# ADS1298.net
KiCad netlist of a schematic drawn in Altium Designer
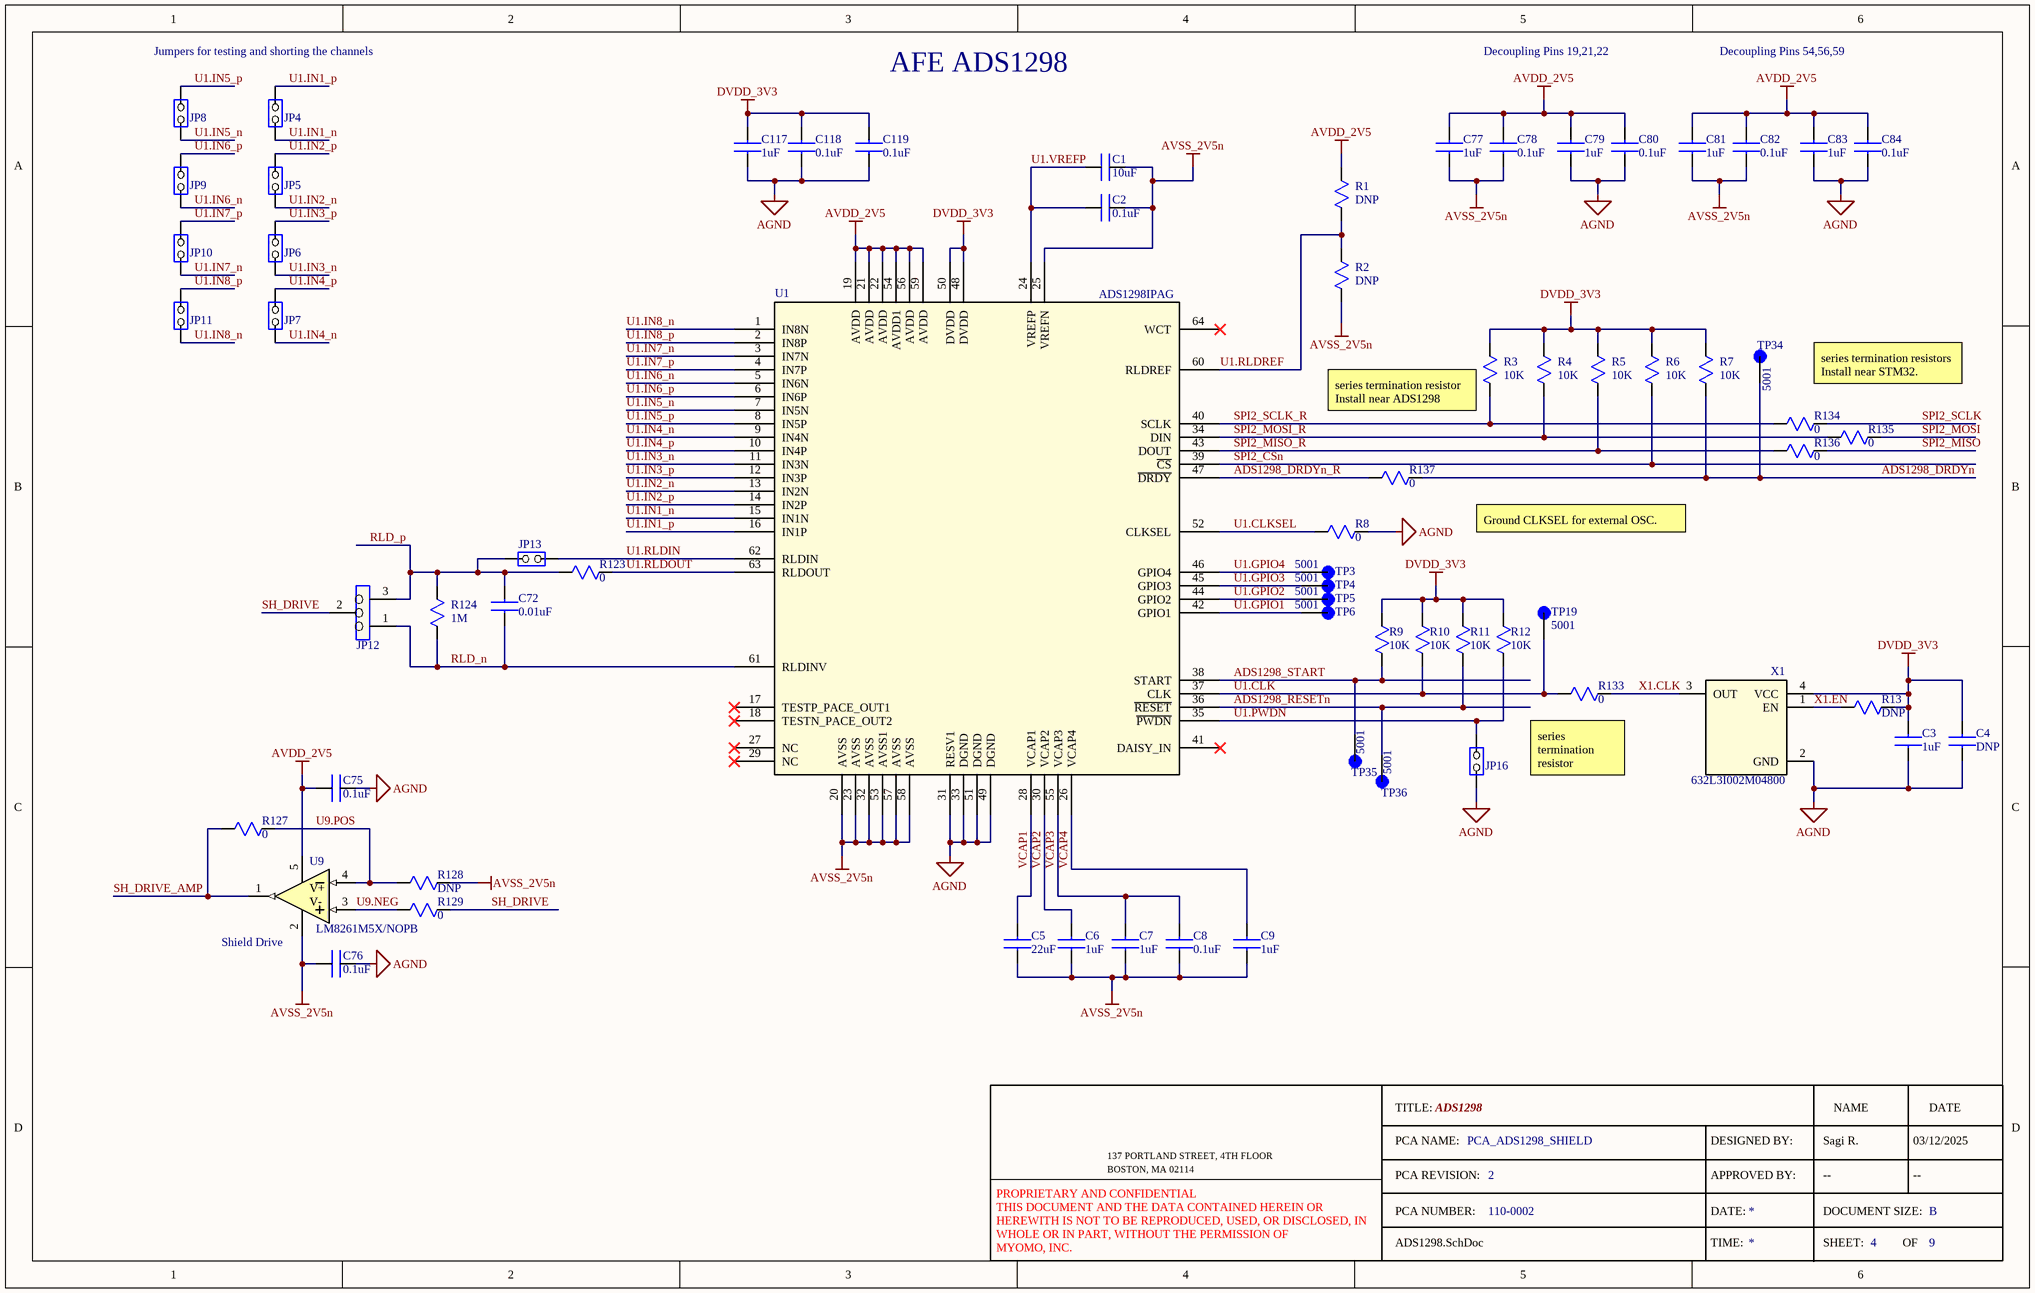
[diagram p0: ADS1298.SchDoc]

(export (version "E")
  (design (tool "Eeschema 10.0.6"))
  (components
    (comp (ref "C1")
      (value "10uF")
      (footprint "1210")
      (description "CAP CER 10UF 25V X7R 1210")
      (fields (field (name "MFG") "SUMSUNG"))
      (libsource (lib "Myomo_SCH_Library") (part "C_1210_CER_10uF_25V_X7R"))
    )
    (comp (ref "C2")
      (value "0.1uF")
      (footprint "0402")
      (description "CAP CER 0.1UF 50V X7R 0402")
      (fields (field (name "MFG") "Samsung"))
      (libsource (lib "") (part "C_0402_CER_0.1uF_50V_X7R_1"))
    )
    (comp (ref "C3")
      (value "1uF")
      (footprint "0603")
      (description "CAP CER 1UF 50V X7R 0603")
      (fields (field (name "MFG") "YAGEO"))
      (libsource (lib "Myomo_SCH_Library") (part "C_0603_CER_1uF_50V_X7R"))
    )
    (comp (ref "C4")
      (value "DNP")
      (footprint "0603")
      (description "CAP CER 0603 DNP")
      (libsource (lib "Myomo_SCH_Library") (part "C_0603_DNP"))
    )
    (comp (ref "C5")
      (value "22uF")
      (footprint "1210")
      (description "CAP CER 22UF 25V X7R 1210")
      (fields (field (name "MFG") "SUMSUNG"))
      (libsource (lib "Myomo_SCH_Library") (part "C_1210_CER_22uF_25V_X7R"))
    )
    (comp (ref "C6")
      (value "1uF")
      (footprint "0603")
      (description "CAP CER 1UF 50V X7R 0603")
      (fields (field (name "MFG") "YAGEO"))
      (libsource (lib "Myomo_SCH_Library") (part "C_0603_CER_1uF_50V_X7R"))
    )
    (comp (ref "C7")
      (value "1uF")
      (footprint "0603")
      (description "CAP CER 1UF 50V X7R 0603")
      (fields (field (name "MFG") "YAGEO"))
      (libsource (lib "Myomo_SCH_Library") (part "C_0603_CER_1uF_50V_X7R"))
    )
    (comp (ref "C8")
      (value "0.1uF")
      (footprint "0402")
      (description "CAP CER 0.1UF 50V X7R 0402")
      (fields (field (name "MFG") "Samsung"))
      (libsource (lib "Myomo_SCH_Library") (part "C_0402_CER_0.1uF_50V_X7R"))
    )
    (comp (ref "C9")
      (value "1uF")
      (footprint "0603")
      (description "CAP CER 1UF 50V X7R 0603")
      (fields (field (name "MFG") "YAGEO"))
      (libsource (lib "Myomo_SCH_Library") (part "C_0603_CER_1uF_50V_X7R"))
    )
    (comp (ref "C72")
      (value "0.01uF")
      (footprint "0603")
      (description "CAP CER 10000PF 100V X7R 0603")
      (fields (field (name "MFG") "SAMSUNG"))
      (libsource (lib "Myomo_SCH_Library") (part "C_0603_CER_0.01uF_100V_X7R"))
    )
    (comp (ref "C75")
      (value "0.1uF")
      (footprint "0402")
      (description "CAP CER 0.1UF 50V X7R 0402")
      (fields (field (name "MFG") "Samsung"))
      (libsource (lib "") (part "C_0402_CER_0.1uF_50V_X7R_1"))
    )
    (comp (ref "C76")
      (value "0.1uF")
      (footprint "0402")
      (description "CAP CER 0.1UF 50V X7R 0402")
      (fields (field (name "MFG") "Samsung"))
      (libsource (lib "") (part "C_0402_CER_0.1uF_50V_X7R_1"))
    )
    (comp (ref "C77")
      (value "1uF")
      (footprint "0603")
      (description "CAP CER 1UF 50V X7R 0603")
      (fields (field (name "MFG") "YAGEO"))
      (libsource (lib "Myomo_SCH_Library") (part "C_0603_CER_1uF_50V_X7R"))
    )
    (comp (ref "C78")
      (value "0.1uF")
      (footprint "0402")
      (description "CAP CER 0.1UF 50V X7R 0402")
      (fields (field (name "MFG") "Samsung"))
      (libsource (lib "Myomo_SCH_Library") (part "C_0402_CER_0.1uF_50V_X7R"))
    )
    (comp (ref "C79")
      (value "1uF")
      (footprint "0603")
      (description "CAP CER 1UF 50V X7R 0603")
      (fields (field (name "MFG") "YAGEO"))
      (libsource (lib "Myomo_SCH_Library") (part "C_0603_CER_1uF_50V_X7R"))
    )
    (comp (ref "C80")
      (value "0.1uF")
      (footprint "0402")
      (description "CAP CER 0.1UF 50V X7R 0402")
      (fields (field (name "MFG") "Samsung"))
      (libsource (lib "Myomo_SCH_Library") (part "C_0402_CER_0.1uF_50V_X7R"))
    )
    (comp (ref "C81")
      (value "1uF")
      (footprint "0603")
      (description "CAP CER 1UF 50V X7R 0603")
      (fields (field (name "MFG") "YAGEO"))
      (libsource (lib "Myomo_SCH_Library") (part "C_0603_CER_1uF_50V_X7R"))
    )
    (comp (ref "C82")
      (value "0.1uF")
      (footprint "0402")
      (description "CAP CER 0.1UF 50V X7R 0402")
      (fields (field (name "MFG") "Samsung"))
      (libsource (lib "Myomo_SCH_Library") (part "C_0402_CER_0.1uF_50V_X7R"))
    )
    (comp (ref "C83")
      (value "1uF")
      (footprint "0603")
      (description "CAP CER 1UF 50V X7R 0603")
      (fields (field (name "MFG") "YAGEO"))
      (libsource (lib "Myomo_SCH_Library") (part "C_0603_CER_1uF_50V_X7R"))
    )
    (comp (ref "C84")
      (value "0.1uF")
      (footprint "0402")
      (description "CAP CER 0.1UF 50V X7R 0402")
      (fields (field (name "MFG") "Samsung"))
      (libsource (lib "Myomo_SCH_Library") (part "C_0402_CER_0.1uF_50V_X7R"))
    )
    (comp (ref "C117")
      (value "1uF")
      (footprint "0603")
      (description "CAP CER 1UF 50V X7R 0603")
      (fields (field (name "MFG") "YAGEO"))
      (libsource (lib "Myomo_SCH_Library") (part "C_0603_CER_1uF_50V_X7R"))
    )
    (comp (ref "C118")
      (value "0.1uF")
      (footprint "0402")
      (description "CAP CER 0.1UF 50V X7R 0402")
      (fields (field (name "MFG") "Samsung"))
      (libsource (lib "Myomo_SCH_Library") (part "C_0402_CER_0.1uF_50V_X7R"))
    )
    (comp (ref "C119")
      (value "0.1uF")
      (footprint "0402")
      (description "CAP CER 0.1UF 50V X7R 0402")
      (fields (field (name "MFG") "Samsung"))
      (libsource (lib "Myomo_SCH_Library") (part "C_0402_CER_0.1uF_50V_X7R"))
    )
    (comp (ref "JP4")
      (value "JP_1x2_TSW-102-07-F-S")
      (footprint "JP_1x2_TSW-102-07-F-S")
      (description "CONN HEADER VERT 2POS 2.54MM")
      (fields (field (name "MFG") "SAMTEC"))
      (libsource (lib "Myomo_SCH_Library") (part "JP_1x2_TSW-102-07-F-S"))
    )
    (comp (ref "JP5")
      (value "JP_1x2_TSW-102-07-F-S")
      (footprint "JP_1x2_TSW-102-07-F-S")
      (description "CONN HEADER VERT 2POS 2.54MM")
      (fields (field (name "MFG") "SAMTEC"))
      (libsource (lib "Myomo_SCH_Library") (part "JP_1x2_TSW-102-07-F-S"))
    )
    (comp (ref "JP6")
      (value "JP_1x2_TSW-102-07-F-S")
      (footprint "JP_1x2_TSW-102-07-F-S")
      (description "CONN HEADER VERT 2POS 2.54MM")
      (fields (field (name "MFG") "SAMTEC"))
      (libsource (lib "Myomo_SCH_Library") (part "JP_1x2_TSW-102-07-F-S"))
    )
    (comp (ref "JP7")
      (value "JP_1x2_TSW-102-07-F-S")
      (footprint "JP_1x2_TSW-102-07-F-S")
      (description "CONN HEADER VERT 2POS 2.54MM")
      (fields (field (name "MFG") "SAMTEC"))
      (libsource (lib "Myomo_SCH_Library") (part "JP_1x2_TSW-102-07-F-S"))
    )
    (comp (ref "JP8")
      (value "JP_1x2_TSW-102-07-F-S")
      (footprint "JP_1x2_TSW-102-07-F-S")
      (description "CONN HEADER VERT 2POS 2.54MM")
      (fields (field (name "MFG") "SAMTEC"))
      (libsource (lib "Myomo_SCH_Library") (part "JP_1x2_TSW-102-07-F-S"))
    )
    (comp (ref "JP9")
      (value "JP_1x2_TSW-102-07-F-S")
      (footprint "JP_1x2_TSW-102-07-F-S")
      (description "CONN HEADER VERT 2POS 2.54MM")
      (fields (field (name "MFG") "SAMTEC"))
      (libsource (lib "Myomo_SCH_Library") (part "JP_1x2_TSW-102-07-F-S"))
    )
    (comp (ref "JP10")
      (value "JP_1x2_TSW-102-07-F-S")
      (footprint "JP_1x2_TSW-102-07-F-S")
      (description "CONN HEADER VERT 2POS 2.54MM")
      (fields (field (name "MFG") "SAMTEC"))
      (libsource (lib "Myomo_SCH_Library") (part "JP_1x2_TSW-102-07-F-S"))
    )
    (comp (ref "JP11")
      (value "JP_1x2_TSW-102-07-F-S")
      (footprint "JP_1x2_TSW-102-07-F-S")
      (description "CONN HEADER VERT 2POS 2.54MM")
      (fields (field (name "MFG") "SAMTEC"))
      (libsource (lib "Myomo_SCH_Library") (part "JP_1x2_TSW-102-07-F-S"))
    )
    (comp (ref "JP12")
      (value "JP_1x3_TSW-103-07-F-S")
      (footprint "JP_1x3_TSW-103-07-F-S")
      (description "CONN HEADER VERT 2POS 2.54MM")
      (fields (field (name "MFG") "SAMTEC"))
      (libsource (lib "Myomo_SCH_Library") (part "JP_1x3_TSW-103-07-F-S"))
    )
    (comp (ref "JP13")
      (value "JP_1x2_TSW-102-07-F-S")
      (footprint "JP_1x2_TSW-102-07-F-S")
      (description "CONN HEADER VERT 2POS 2.54MM")
      (fields (field (name "MFG") "SAMTEC"))
      (libsource (lib "Myomo_SCH_Library") (part "JP_1x2_TSW-102-07-F-S"))
    )
    (comp (ref "JP16")
      (value "JP_1x2_TSW-102-07-F-S")
      (footprint "JP_1x2_TSW-102-07-F-S")
      (description "CONN HEADER VERT 2POS 2.54MM")
      (fields (field (name "MFG") "SAMTEC"))
      (libsource (lib "Myomo_SCH_Library") (part "JP_1x2_TSW-102-07-F-S"))
    )
    (comp (ref "R1")
      (value "DNP")
      (footprint "0402")
      (description "RES 0402 DNP")
      (libsource (lib "Myomo_SCH_Library") (part "R_0402_DNP"))
    )
    (comp (ref "R2")
      (value "DNP")
      (footprint "0402")
      (description "RES 0402 DNP")
      (libsource (lib "Myomo_SCH_Library") (part "R_0402_DNP"))
    )
    (comp (ref "R3")
      (value "10K")
      (footprint "0402")
      (description "RES SMD 10K OHM 1% 1/10W 0402")
      (fields (field (name "MFG") "Panasonic"))
      (libsource (lib "Myomo_SCH_Library") (part "R_0402_10K_1%_1/10W"))
    )
    (comp (ref "R4")
      (value "10K")
      (footprint "0402")
      (description "RES SMD 10K OHM 1% 1/10W 0402")
      (fields (field (name "MFG") "Panasonic"))
      (libsource (lib "Myomo_SCH_Library") (part "R_0402_10K_1%_1/10W"))
    )
    (comp (ref "R5")
      (value "10K")
      (footprint "0402")
      (description "RES SMD 10K OHM 1% 1/10W 0402")
      (fields (field (name "MFG") "Panasonic"))
      (libsource (lib "Myomo_SCH_Library") (part "R_0402_10K_1%_1/10W"))
    )
    (comp (ref "R6")
      (value "10K")
      (footprint "0402")
      (description "RES SMD 10K OHM 1% 1/10W 0402")
      (fields (field (name "MFG") "Panasonic"))
      (libsource (lib "Myomo_SCH_Library") (part "R_0402_10K_1%_1/10W"))
    )
    (comp (ref "R7")
      (value "10K")
      (footprint "0402")
      (description "RES SMD 10K OHM 1% 1/10W 0402")
      (fields (field (name "MFG") "Panasonic"))
      (libsource (lib "Myomo_SCH_Library") (part "R_0402_10K_1%_1/10W"))
    )
    (comp (ref "R8")
      (value "0")
      (footprint "0603")
      (description "RES 0 OHM JUMPER 1/10W 0603")
      (fields (field (name "MFG") "YAGEO"))
      (libsource (lib "Myomo_SCH_Library") (part "R_0603_0"))
    )
    (comp (ref "R9")
      (value "10K")
      (footprint "0402")
      (description "RES SMD 10K OHM 1% 1/10W 0402")
      (fields (field (name "MFG") "Panasonic"))
      (libsource (lib "Myomo_SCH_Library") (part "R_0402_10K_1%_1/10W"))
    )
    (comp (ref "R10")
      (value "10K")
      (footprint "0402")
      (description "RES SMD 10K OHM 1% 1/10W 0402")
      (fields (field (name "MFG") "Panasonic"))
      (libsource (lib "Myomo_SCH_Library") (part "R_0402_10K_1%_1/10W"))
    )
    (comp (ref "R11")
      (value "10K")
      (footprint "0402")
      (description "RES SMD 10K OHM 1% 1/10W 0402")
      (fields (field (name "MFG") "Panasonic"))
      (libsource (lib "Myomo_SCH_Library") (part "R_0402_10K_1%_1/10W"))
    )
    (comp (ref "R12")
      (value "10K")
      (footprint "0402")
      (description "RES SMD 10K OHM 1% 1/10W 0402")
      (fields (field (name "MFG") "Panasonic"))
      (libsource (lib "Myomo_SCH_Library") (part "R_0402_10K_1%_1/10W"))
    )
    (comp (ref "R13")
      (value "DNP")
      (footprint "0603")
      (description "RES 0603 DNP")
      (libsource (lib "Myomo_SCH_Library") (part "R_0603_DNP"))
    )
    (comp (ref "R123")
      (value "0")
      (footprint "0603")
      (description "RES 0 OHM JUMPER 1/10W 0603")
      (fields (field (name "MFG") "YAGEO"))
      (libsource (lib "Myomo_SCH_Library") (part "R_0603_0"))
    )
    (comp (ref "R124")
      (value "1M")
      (footprint "0402")
      (description "RES SMD 1M OHM 1% 1/10W 0402")
      (fields (field (name "MFG") "Panasonic"))
      (libsource (lib "Myomo_SCH_Library") (part "R_0402_1M_1%_1/10W"))
    )
    (comp (ref "R127")
      (value "0")
      (footprint "0402")
      (description "RES 0 OHM JUMPER 1/10W 0402")
      (fields (field (name "MFG") "YAGEO"))
      (libsource (lib "Myomo_SCH_Library") (part "R_0402_0"))
    )
    (comp (ref "R128")
      (value "DNP")
      (footprint "0402")
      (description "RES 0402 DNP")
      (libsource (lib "") (part "R_0402_DNP_1"))
    )
    (comp (ref "R129")
      (value "0")
      (footprint "0402")
      (description "RES 0 OHM JUMPER 1/10W 0402")
      (fields (field (name "MFG") "YAGEO"))
      (libsource (lib "Myomo_SCH_Library") (part "R_0402_0"))
    )
    (comp (ref "R133")
      (value "0")
      (footprint "0603")
      (description "RES 0 OHM JUMPER 1/10W 0603")
      (fields (field (name "MFG") "YAGEO"))
      (libsource (lib "Myomo_SCH_Library") (part "R_0603_0"))
    )
    (comp (ref "R134")
      (value "0")
      (footprint "0402")
      (description "RES 0 OHM JUMPER 1/10W 0402")
      (fields (field (name "MFG") "YAGEO"))
      (libsource (lib "Myomo_SCH_Library") (part "R_0402_0"))
    )
    (comp (ref "R135")
      (value "0")
      (footprint "0402")
      (description "RES 0 OHM JUMPER 1/10W 0402")
      (fields (field (name "MFG") "YAGEO"))
      (libsource (lib "Myomo_SCH_Library") (part "R_0402_0"))
    )
    (comp (ref "R136")
      (value "0")
      (footprint "0402")
      (description "RES 0 OHM JUMPER 1/10W 0402")
      (fields (field (name "MFG") "YAGEO"))
      (libsource (lib "Myomo_SCH_Library") (part "R_0402_0"))
    )
    (comp (ref "R137")
      (value "0")
      (footprint "0603")
      (description "RES 0 OHM JUMPER 1/10W 0603")
      (fields (field (name "MFG") "YAGEO"))
      (libsource (lib "Myomo_SCH_Library") (part "R_0603_0"))
    )
    (comp (ref "TP3")
      (value "5001")
      (footprint "TP_CLIP_BLK_5001")
      (description "PC TEST POINT MINIATURE BLACK")
      (fields (field (name "MFG") "Keystone Electronics"))
      (libsource (lib "Myomo_SCH_Library") (part "TP_CLIP_BLK_5001"))
    )
    (comp (ref "TP4")
      (value "5001")
      (footprint "TP_CLIP_BLK_5001")
      (description "PC TEST POINT MINIATURE BLACK")
      (fields (field (name "MFG") "Keystone Electronics"))
      (libsource (lib "Myomo_SCH_Library") (part "TP_CLIP_BLK_5001"))
    )
    (comp (ref "TP5")
      (value "5001")
      (footprint "TP_CLIP_BLK_5001")
      (description "PC TEST POINT MINIATURE BLACK")
      (fields (field (name "MFG") "Keystone Electronics"))
      (libsource (lib "Myomo_SCH_Library") (part "TP_CLIP_BLK_5001"))
    )
    (comp (ref "TP6")
      (value "5001")
      (footprint "TP_CLIP_BLK_5001")
      (description "PC TEST POINT MINIATURE BLACK")
      (fields (field (name "MFG") "Keystone Electronics"))
      (libsource (lib "Myomo_SCH_Library") (part "TP_CLIP_BLK_5001"))
    )
    (comp (ref "TP19")
      (value "5001")
      (footprint "TP_CLIP_BLK_5001")
      (description "PC TEST POINT MINIATURE BLACK")
      (fields (field (name "MFG") "Keystone Electronics"))
      (libsource (lib "Myomo_SCH_Library") (part "TP_CLIP_BLK_5001"))
    )
    (comp (ref "TP34")
      (value "5001")
      (footprint "TP_CLIP_BLK_5001")
      (description "PC TEST POINT MINIATURE BLACK")
      (fields (field (name "MFG") "Keystone Electronics"))
      (libsource (lib "Myomo_SCH_Library") (part "TP_CLIP_BLK_5001"))
    )
    (comp (ref "TP35")
      (value "5001")
      (footprint "TP_CLIP_BLK_5001")
      (description "PC TEST POINT MINIATURE BLACK")
      (fields (field (name "MFG") "Keystone Electronics"))
      (libsource (lib "Myomo_SCH_Library") (part "TP_CLIP_BLK_5001"))
    )
    (comp (ref "TP36")
      (value "5001")
      (footprint "TP_CLIP_BLK_5001")
      (description "PC TEST POINT MINIATURE BLACK")
      (fields (field (name "MFG") "Keystone Electronics"))
      (libsource (lib "Myomo_SCH_Library") (part "TP_CLIP_BLK_5001"))
    )
    (comp (ref "U1")
      (value "ADS1298IPAG")
      (footprint "U_ADS1298IPAG")
      (description "8-Channel 24-bit ADC With Integrated ECG Front End")
      (fields (field (name "MFG") "TI"))
      (libsource (lib "Myomo_SCH_Library") (part "U_ADS1298IPAG"))
    )
    (comp (ref "U9")
      (value "LM8261M5X/NOPB")
      (footprint "U_LM8261M5X/NOPB")
      (description "IC OPAMP GP 1 CIRCUIT SOT23-5")
      (fields (field (name "MFG") "Texas Instruments"))
      (libsource (lib "Myomo_SCH_Library") (part "U_LM8261M5X/NOPB"))
    )
    (comp (ref "X1")
      (value "632L3I002M04800")
      (footprint "XTAL_2.048MHZ_50PPM_3.3V")
      (description "XTAL OSC XO 2.0480MHZ HCMOS SMD")
      (fields (field (name "MFG") "CTS"))
      (libsource (lib "Myomo_SCH_Library") (part "XTAL_2.048MHZ_50PPM_3.3V"))
    )
  )
  (nets
    (net (code "1") (name "/ADS1298_DRDYn") (class "Default")
      (node (ref "R137") (pin "2") (pinfunction "2_2") (pintype "passive"))
      (node (ref "R7") (pin "2") (pinfunction "2_2") (pintype "passive"))
      (node (ref "TP34") (pin "TP") (pinfunction "TP_TP") (pintype "passive"))
    )
    (net (code "2") (name "/ADS1298_DRDYn_R") (class "Default")
      (node (ref "R137") (pin "1") (pinfunction "1_1") (pintype "passive"))
      (node (ref "U1") (pin "47") (pinfunction "~{DRDY}_47") (pintype "passive"))
    )
    (net (code "3") (name "/ADS1298_RESETn") (class "Default")
      (node (ref "R11") (pin "2") (pinfunction "2_2") (pintype "passive"))
      (node (ref "TP36") (pin "TP") (pinfunction "TP_TP") (pintype "passive"))
      (node (ref "U1") (pin "36") (pinfunction "~{RESET}_36") (pintype "passive"))
    )
    (net (code "4") (name "/ADS1298_START") (class "Default")
      (node (ref "R9") (pin "2") (pinfunction "2_2") (pintype "passive"))
      (node (ref "TP35") (pin "TP") (pinfunction "TP_TP") (pintype "passive"))
      (node (ref "U1") (pin "38") (pinfunction "START_38") (pintype "passive"))
    )
    (net (code "5") (name "/RLD_n") (class "Default")
      (node (ref "C72") (pin "2") (pinfunction "2_2") (pintype "passive"))
      (node (ref "JP12") (pin "1") (pinfunction "1_1") (pintype "passive"))
      (node (ref "R124") (pin "2") (pinfunction "2_2") (pintype "passive"))
      (node (ref "U1") (pin "61") (pinfunction "RLDINV_61") (pintype "passive"))
    )
    (net (code "6") (name "/RLD_p") (class "Default")
      (node (ref "C72") (pin "1") (pinfunction "1_1") (pintype "passive"))
      (node (ref "JP12") (pin "3") (pinfunction "3_3") (pintype "passive"))
      (node (ref "JP13") (pin "1") (pinfunction "1_1") (pintype "passive"))
      (node (ref "R123") (pin "1") (pinfunction "1_1") (pintype "passive"))
      (node (ref "R124") (pin "1") (pinfunction "1_1") (pintype "passive"))
    )
    (net (code "7") (name "/SH_DRIVE") (class "Default")
      (node (ref "JP12") (pin "2") (pinfunction "2_2") (pintype "passive"))
      (node (ref "R129") (pin "2") (pinfunction "2_2") (pintype "passive"))
    )
    (net (code "8") (name "/SH_DRIVE_AMP") (class "Default")
      (node (ref "R127") (pin "1") (pinfunction "1_1") (pintype "passive"))
      (node (ref "U9") (pin "1") (pinfunction "OUT_1") (pintype "output"))
    )
    (net (code "9") (name "/SPI2_CSn") (class "Default")
      (node (ref "R6") (pin "2") (pinfunction "2_2") (pintype "passive"))
      (node (ref "U1") (pin "39") (pinfunction "~{CS}_39") (pintype "passive"))
    )
    (net (code "10") (name "/SPI2_MISO") (class "Default")
      (node (ref "R136") (pin "2") (pinfunction "2_2") (pintype "passive"))
    )
    (net (code "11") (name "/SPI2_MISO_R") (class "Default")
      (node (ref "R136") (pin "1") (pinfunction "1_1") (pintype "passive"))
      (node (ref "R5") (pin "2") (pinfunction "2_2") (pintype "passive"))
      (node (ref "U1") (pin "43") (pinfunction "DOUT_43") (pintype "passive"))
    )
    (net (code "12") (name "/SPI2_MOSI") (class "Default")
      (node (ref "R135") (pin "2") (pinfunction "2_2") (pintype "passive"))
    )
    (net (code "13") (name "/SPI2_MOSI_R") (class "Default")
      (node (ref "R135") (pin "1") (pinfunction "1_1") (pintype "passive"))
      (node (ref "R4") (pin "2") (pinfunction "2_2") (pintype "passive"))
      (node (ref "U1") (pin "34") (pinfunction "DIN_34") (pintype "passive"))
    )
    (net (code "14") (name "/SPI2_SCLK") (class "Default")
      (node (ref "R134") (pin "2") (pinfunction "2_2") (pintype "passive"))
    )
    (net (code "15") (name "/SPI2_SCLK_R") (class "Default")
      (node (ref "R134") (pin "1") (pinfunction "1_1") (pintype "passive"))
      (node (ref "R3") (pin "2") (pinfunction "2_2") (pintype "passive"))
      (node (ref "U1") (pin "40") (pinfunction "SCLK_40") (pintype "passive"))
    )
    (net (code "16") (name "/U1.CLK") (class "Default")
      (node (ref "R10") (pin "2") (pinfunction "2_2") (pintype "passive"))
      (node (ref "R133") (pin "1") (pinfunction "1_1") (pintype "passive"))
      (node (ref "TP19") (pin "TP") (pinfunction "TP_TP") (pintype "passive"))
      (node (ref "U1") (pin "37") (pinfunction "CLK_37") (pintype "passive"))
    )
    (net (code "17") (name "/U1.CLKSEL") (class "Default")
      (node (ref "R8") (pin "1") (pinfunction "1_1") (pintype "passive"))
      (node (ref "U1") (pin "52") (pinfunction "CLKSEL_52") (pintype "passive"))
    )
    (net (code "18") (name "/U1.GPIO1") (class "Default")
      (node (ref "TP6") (pin "TP") (pinfunction "TP_TP") (pintype "passive"))
      (node (ref "U1") (pin "42") (pinfunction "GPIO1_42") (pintype "passive"))
    )
    (net (code "19") (name "/U1.GPIO2") (class "Default")
      (node (ref "TP5") (pin "TP") (pinfunction "TP_TP") (pintype "passive"))
      (node (ref "U1") (pin "44") (pinfunction "GPIO2_44") (pintype "passive"))
    )
    (net (code "20") (name "/U1.GPIO3") (class "Default")
      (node (ref "TP4") (pin "TP") (pinfunction "TP_TP") (pintype "passive"))
      (node (ref "U1") (pin "45") (pinfunction "GPIO3_45") (pintype "passive"))
    )
    (net (code "21") (name "/U1.GPIO4") (class "Default")
      (node (ref "TP3") (pin "TP") (pinfunction "TP_TP") (pintype "passive"))
      (node (ref "U1") (pin "46") (pinfunction "GPIO4_46") (pintype "passive"))
    )
    (net (code "22") (name "/U1.IN1_n") (class "Default")
      (node (ref "JP4") (pin "2") (pinfunction "2_2") (pintype "passive"))
      (node (ref "U1") (pin "15") (pinfunction "IN1N_15") (pintype "passive"))
    )
    (net (code "23") (name "/U1.IN1_p") (class "Default")
      (node (ref "JP4") (pin "1") (pinfunction "1_1") (pintype "passive"))
      (node (ref "U1") (pin "16") (pinfunction "IN1P_16") (pintype "passive"))
    )
    (net (code "24") (name "/U1.IN2_n") (class "Default")
      (node (ref "JP5") (pin "2") (pinfunction "2_2") (pintype "passive"))
      (node (ref "U1") (pin "13") (pinfunction "IN2N_13") (pintype "passive"))
    )
    (net (code "25") (name "/U1.IN2_p") (class "Default")
      (node (ref "JP5") (pin "1") (pinfunction "1_1") (pintype "passive"))
      (node (ref "U1") (pin "14") (pinfunction "IN2P_14") (pintype "passive"))
    )
    (net (code "26") (name "/U1.IN3_n") (class "Default")
      (node (ref "JP6") (pin "2") (pinfunction "2_2") (pintype "passive"))
      (node (ref "U1") (pin "11") (pinfunction "IN3N_11") (pintype "passive"))
    )
    (net (code "27") (name "/U1.IN3_p") (class "Default")
      (node (ref "JP6") (pin "1") (pinfunction "1_1") (pintype "passive"))
      (node (ref "U1") (pin "12") (pinfunction "IN3P_12") (pintype "passive"))
    )
    (net (code "28") (name "/U1.IN4_n") (class "Default")
      (node (ref "JP7") (pin "2") (pinfunction "2_2") (pintype "passive"))
      (node (ref "U1") (pin "9") (pinfunction "IN4N_9") (pintype "passive"))
    )
    (net (code "29") (name "/U1.IN4_p") (class "Default")
      (node (ref "JP7") (pin "1") (pinfunction "1_1") (pintype "passive"))
      (node (ref "U1") (pin "10") (pinfunction "IN4P_10") (pintype "passive"))
    )
    (net (code "30") (name "/U1.IN5_n") (class "Default")
      (node (ref "JP8") (pin "2") (pinfunction "2_2") (pintype "passive"))
      (node (ref "U1") (pin "7") (pinfunction "IN5N_7") (pintype "passive"))
    )
    (net (code "31") (name "/U1.IN5_p") (class "Default")
      (node (ref "JP8") (pin "1") (pinfunction "1_1") (pintype "passive"))
      (node (ref "U1") (pin "8") (pinfunction "IN5P_8") (pintype "passive"))
    )
    (net (code "32") (name "/U1.IN6_n") (class "Default")
      (node (ref "JP9") (pin "2") (pinfunction "2_2") (pintype "passive"))
      (node (ref "U1") (pin "5") (pinfunction "IN6N_5") (pintype "passive"))
    )
    (net (code "33") (name "/U1.IN6_p") (class "Default")
      (node (ref "JP9") (pin "1") (pinfunction "1_1") (pintype "passive"))
      (node (ref "U1") (pin "6") (pinfunction "IN6P_6") (pintype "passive"))
    )
    (net (code "34") (name "/U1.IN7_n") (class "Default")
      (node (ref "JP10") (pin "2") (pinfunction "2_2") (pintype "passive"))
      (node (ref "U1") (pin "3") (pinfunction "IN7N_3") (pintype "passive"))
    )
    (net (code "35") (name "/U1.IN7_p") (class "Default")
      (node (ref "JP10") (pin "1") (pinfunction "1_1") (pintype "passive"))
      (node (ref "U1") (pin "4") (pinfunction "IN7P_4") (pintype "passive"))
    )
    (net (code "36") (name "/U1.IN8_n") (class "Default")
      (node (ref "JP11") (pin "2") (pinfunction "2_2") (pintype "passive"))
      (node (ref "U1") (pin "1") (pinfunction "IN8N_1") (pintype "passive"))
    )
    (net (code "37") (name "/U1.IN8_p") (class "Default")
      (node (ref "JP11") (pin "1") (pinfunction "1_1") (pintype "passive"))
      (node (ref "U1") (pin "2") (pinfunction "IN8P_2") (pintype "passive"))
    )
    (net (code "38") (name "/U1.PWDN") (class "Default")
      (node (ref "JP16") (pin "2") (pinfunction "2_2") (pintype "passive"))
      (node (ref "R12") (pin "2") (pinfunction "2_2") (pintype "passive"))
      (node (ref "U1") (pin "35") (pinfunction "~{PWDN}_35") (pintype "passive"))
    )
    (net (code "39") (name "/U1.RLDIN") (class "Default")
      (node (ref "JP13") (pin "2") (pinfunction "2_2") (pintype "passive"))
      (node (ref "U1") (pin "62") (pinfunction "RLDIN_62") (pintype "passive"))
    )
    (net (code "40") (name "/U1.RLDOUT") (class "Default")
      (node (ref "R123") (pin "2") (pinfunction "2_2") (pintype "passive"))
      (node (ref "U1") (pin "63") (pinfunction "RLDOUT_63") (pintype "passive"))
    )
    (net (code "41") (name "/U1.RLDREF") (class "Default")
      (node (ref "R1") (pin "2") (pinfunction "2_2") (pintype "passive"))
      (node (ref "R2") (pin "1") (pinfunction "1_1") (pintype "passive"))
      (node (ref "U1") (pin "60") (pinfunction "RLDREF_60") (pintype "passive"))
    )
    (net (code "42") (name "/U1.VREFP") (class "Default")
      (node (ref "C1") (pin "1") (pinfunction "1_1") (pintype "passive"))
      (node (ref "C2") (pin "1") (pinfunction "1_1") (pintype "passive"))
      (node (ref "U1") (pin "24") (pinfunction "VREFP_24") (pintype "power_in"))
    )
    (net (code "43") (name "/U9.NEG") (class "Default")
      (node (ref "R129") (pin "1") (pinfunction "1_1") (pintype "passive"))
      (node (ref "U9") (pin "3") (pinfunction "IN+_3") (pintype "input"))
    )
    (net (code "44") (name "/U9.POS") (class "Default")
      (node (ref "R127") (pin "2") (pinfunction "2_2") (pintype "passive"))
      (node (ref "R128") (pin "1") (pinfunction "1_1") (pintype "passive"))
      (node (ref "U9") (pin "4") (pinfunction "IN-_4") (pintype "input"))
    )
    (net (code "45") (name "/VCAP1") (class "Default")
      (node (ref "C5") (pin "1") (pinfunction "1_1") (pintype "passive"))
      (node (ref "U1") (pin "28") (pinfunction "VCAP1_28") (pintype "power_in"))
    )
    (net (code "46") (name "/VCAP2") (class "Default")
      (node (ref "C6") (pin "1") (pinfunction "1_1") (pintype "passive"))
      (node (ref "U1") (pin "30") (pinfunction "VCAP2_30") (pintype "power_in"))
    )
    (net (code "47") (name "/VCAP3") (class "Default")
      (node (ref "C7") (pin "1") (pinfunction "1_1") (pintype "passive"))
      (node (ref "C8") (pin "1") (pinfunction "1_1") (pintype "passive"))
      (node (ref "U1") (pin "55") (pinfunction "VCAP3_55") (pintype "power_in"))
    )
    (net (code "48") (name "/VCAP4") (class "Default")
      (node (ref "C9") (pin "1") (pinfunction "1_1") (pintype "passive"))
      (node (ref "U1") (pin "26") (pinfunction "VCAP4_26") (pintype "power_in"))
    )
    (net (code "49") (name "/X1.CLK") (class "Default")
      (node (ref "R133") (pin "2") (pinfunction "2_2") (pintype "passive"))
      (node (ref "X1") (pin "3") (pinfunction "OUT_3") (pintype "passive"))
    )
    (net (code "50") (name "/X1.EN") (class "Default")
      (node (ref "R13") (pin "1") (pinfunction "1_1") (pintype "passive"))
      (node (ref "X1") (pin "1") (pinfunction "EN_1") (pintype "passive"))
    )
    (net (code "51") (name "AGND") (class "Default")
      (node (ref "C117") (pin "2") (pinfunction "2_2") (pintype "passive"))
      (node (ref "C118") (pin "2") (pinfunction "2_2") (pintype "passive"))
      (node (ref "C119") (pin "2") (pinfunction "2_2") (pintype "passive"))
      (node (ref "C3") (pin "2") (pinfunction "2_2") (pintype "passive"))
      (node (ref "C4") (pin "2") (pinfunction "2_2") (pintype "passive"))
      (node (ref "C75") (pin "2") (pinfunction "2_2") (pintype "passive"))
      (node (ref "C76") (pin "2") (pinfunction "2_2") (pintype "passive"))
      (node (ref "C79") (pin "2") (pinfunction "2_2") (pintype "passive"))
      (node (ref "C80") (pin "2") (pinfunction "2_2") (pintype "passive"))
      (node (ref "C83") (pin "2") (pinfunction "2_2") (pintype "passive"))
      (node (ref "C84") (pin "2") (pinfunction "2_2") (pintype "passive"))
      (node (ref "JP16") (pin "1") (pinfunction "1_1") (pintype "passive"))
      (node (ref "R8") (pin "2") (pinfunction "2_2") (pintype "passive"))
      (node (ref "U1") (pin "31") (pinfunction "RESV1_31") (pintype "passive"))
      (node (ref "U1") (pin "33") (pinfunction "DGND_33") (pintype "power_in"))
      (node (ref "U1") (pin "49") (pinfunction "DGND_49") (pintype "power_in"))
      (node (ref "U1") (pin "51") (pinfunction "DGND_51") (pintype "power_in"))
      (node (ref "X1") (pin "2") (pinfunction "GND_2") (pintype "passive"))
    )
    (net (code "52") (name "AVDD_2V5") (class "Default")
      (node (ref "C75") (pin "1") (pinfunction "1_1") (pintype "passive"))
      (node (ref "C77") (pin "1") (pinfunction "1_1") (pintype "passive"))
      (node (ref "C78") (pin "1") (pinfunction "1_1") (pintype "passive"))
      (node (ref "C79") (pin "1") (pinfunction "1_1") (pintype "passive"))
      (node (ref "C80") (pin "1") (pinfunction "1_1") (pintype "passive"))
      (node (ref "C81") (pin "1") (pinfunction "1_1") (pintype "passive"))
      (node (ref "C82") (pin "1") (pinfunction "1_1") (pintype "passive"))
      (node (ref "C83") (pin "1") (pinfunction "1_1") (pintype "passive"))
      (node (ref "C84") (pin "1") (pinfunction "1_1") (pintype "passive"))
      (node (ref "R1") (pin "1") (pinfunction "1_1") (pintype "passive"))
      (node (ref "U1") (pin "19") (pinfunction "AVDD_19") (pintype "power_in"))
      (node (ref "U1") (pin "21") (pinfunction "AVDD_21") (pintype "power_in"))
      (node (ref "U1") (pin "22") (pinfunction "AVDD_22") (pintype "power_in"))
      (node (ref "U1") (pin "54") (pinfunction "AVDD1_54") (pintype "power_in"))
      (node (ref "U1") (pin "56") (pinfunction "AVDD_56") (pintype "power_in"))
      (node (ref "U1") (pin "59") (pinfunction "AVDD_59") (pintype "power_in"))
      (node (ref "U9") (pin "5") (pinfunction "V+_5") (pintype "power_in"))
    )
    (net (code "53") (name "AVSS_2V5n") (class "Default")
      (node (ref "C1") (pin "2") (pinfunction "2_2") (pintype "passive"))
      (node (ref "C2") (pin "2") (pinfunction "2_2") (pintype "passive"))
      (node (ref "C5") (pin "2") (pinfunction "2_2") (pintype "passive"))
      (node (ref "C6") (pin "2") (pinfunction "2_2") (pintype "passive"))
      (node (ref "C7") (pin "2") (pinfunction "2_2") (pintype "passive"))
      (node (ref "C76") (pin "1") (pinfunction "1_1") (pintype "passive"))
      (node (ref "C77") (pin "2") (pinfunction "2_2") (pintype "passive"))
      (node (ref "C78") (pin "2") (pinfunction "2_2") (pintype "passive"))
      (node (ref "C8") (pin "2") (pinfunction "2_2") (pintype "passive"))
      (node (ref "C81") (pin "2") (pinfunction "2_2") (pintype "passive"))
      (node (ref "C82") (pin "2") (pinfunction "2_2") (pintype "passive"))
      (node (ref "C9") (pin "2") (pinfunction "2_2") (pintype "passive"))
      (node (ref "R128") (pin "2") (pinfunction "2_2") (pintype "passive"))
      (node (ref "R2") (pin "2") (pinfunction "2_2") (pintype "passive"))
      (node (ref "U1") (pin "20") (pinfunction "AVSS_20") (pintype "power_in"))
      (node (ref "U1") (pin "23") (pinfunction "AVSS_23") (pintype "power_in"))
      (node (ref "U1") (pin "25") (pinfunction "VREFN_25") (pintype "power_in"))
      (node (ref "U1") (pin "32") (pinfunction "AVSS_32") (pintype "power_in"))
      (node (ref "U1") (pin "53") (pinfunction "AVSS1_53") (pintype "power_in"))
      (node (ref "U1") (pin "57") (pinfunction "AVSS_57") (pintype "power_in"))
      (node (ref "U1") (pin "58") (pinfunction "AVSS_58") (pintype "power_in"))
      (node (ref "U9") (pin "2") (pinfunction "V-_2") (pintype "power_in"))
    )
    (net (code "54") (name "DVDD_3V3") (class "Default")
      (node (ref "C117") (pin "1") (pinfunction "1_1") (pintype "passive"))
      (node (ref "C118") (pin "1") (pinfunction "1_1") (pintype "passive"))
      (node (ref "C119") (pin "1") (pinfunction "1_1") (pintype "passive"))
      (node (ref "C3") (pin "1") (pinfunction "1_1") (pintype "passive"))
      (node (ref "C4") (pin "1") (pinfunction "1_1") (pintype "passive"))
      (node (ref "R10") (pin "1") (pinfunction "1_1") (pintype "passive"))
      (node (ref "R11") (pin "1") (pinfunction "1_1") (pintype "passive"))
      (node (ref "R12") (pin "1") (pinfunction "1_1") (pintype "passive"))
      (node (ref "R13") (pin "2") (pinfunction "2_2") (pintype "passive"))
      (node (ref "R3") (pin "1") (pinfunction "1_1") (pintype "passive"))
      (node (ref "R4") (pin "1") (pinfunction "1_1") (pintype "passive"))
      (node (ref "R5") (pin "1") (pinfunction "1_1") (pintype "passive"))
      (node (ref "R6") (pin "1") (pinfunction "1_1") (pintype "passive"))
      (node (ref "R7") (pin "1") (pinfunction "1_1") (pintype "passive"))
      (node (ref "R9") (pin "1") (pinfunction "1_1") (pintype "passive"))
      (node (ref "U1") (pin "48") (pinfunction "DVDD_48") (pintype "power_in"))
      (node (ref "U1") (pin "50") (pinfunction "DVDD_50") (pintype "power_in"))
      (node (ref "X1") (pin "4") (pinfunction "VCC_4") (pintype "passive"))
    )
    (net (code "55") (name "unconnected-(U1-DAISY_IN-Pad41)") (class "Default")
      (node (ref "U1") (pin "41") (pinfunction "DAISY_IN_41") (pintype "passive+no_connect"))
    )
    (net (code "56") (name "unconnected-(U1-NC-Pad27)") (class "Default")
      (node (ref "U1") (pin "27") (pinfunction "NC_27") (pintype "passive+no_connect"))
    )
    (net (code "57") (name "unconnected-(U1-NC-Pad29)") (class "Default")
      (node (ref "U1") (pin "29") (pinfunction "NC_29") (pintype "passive+no_connect"))
    )
    (net (code "58") (name "unconnected-(U1-TESTN_PACE_OUT2-Pad18)") (class "Default")
      (node (ref "U1") (pin "18") (pinfunction "TESTN_PACE_OUT2_18") (pintype "passive+no_connect"))
    )
    (net (code "59") (name "unconnected-(U1-TESTP_PACE_OUT1-Pad17)") (class "Default")
      (node (ref "U1") (pin "17") (pinfunction "TESTP_PACE_OUT1_17") (pintype "passive+no_connect"))
    )
    (net (code "60") (name "unconnected-(U1-WCT-Pad64)") (class "Default")
      (node (ref "U1") (pin "64") (pinfunction "WCT_64") (pintype "passive+no_connect"))
    )
  )
)
